# fboard.net
KiCad netlist of a schematic drawn in EAGLE
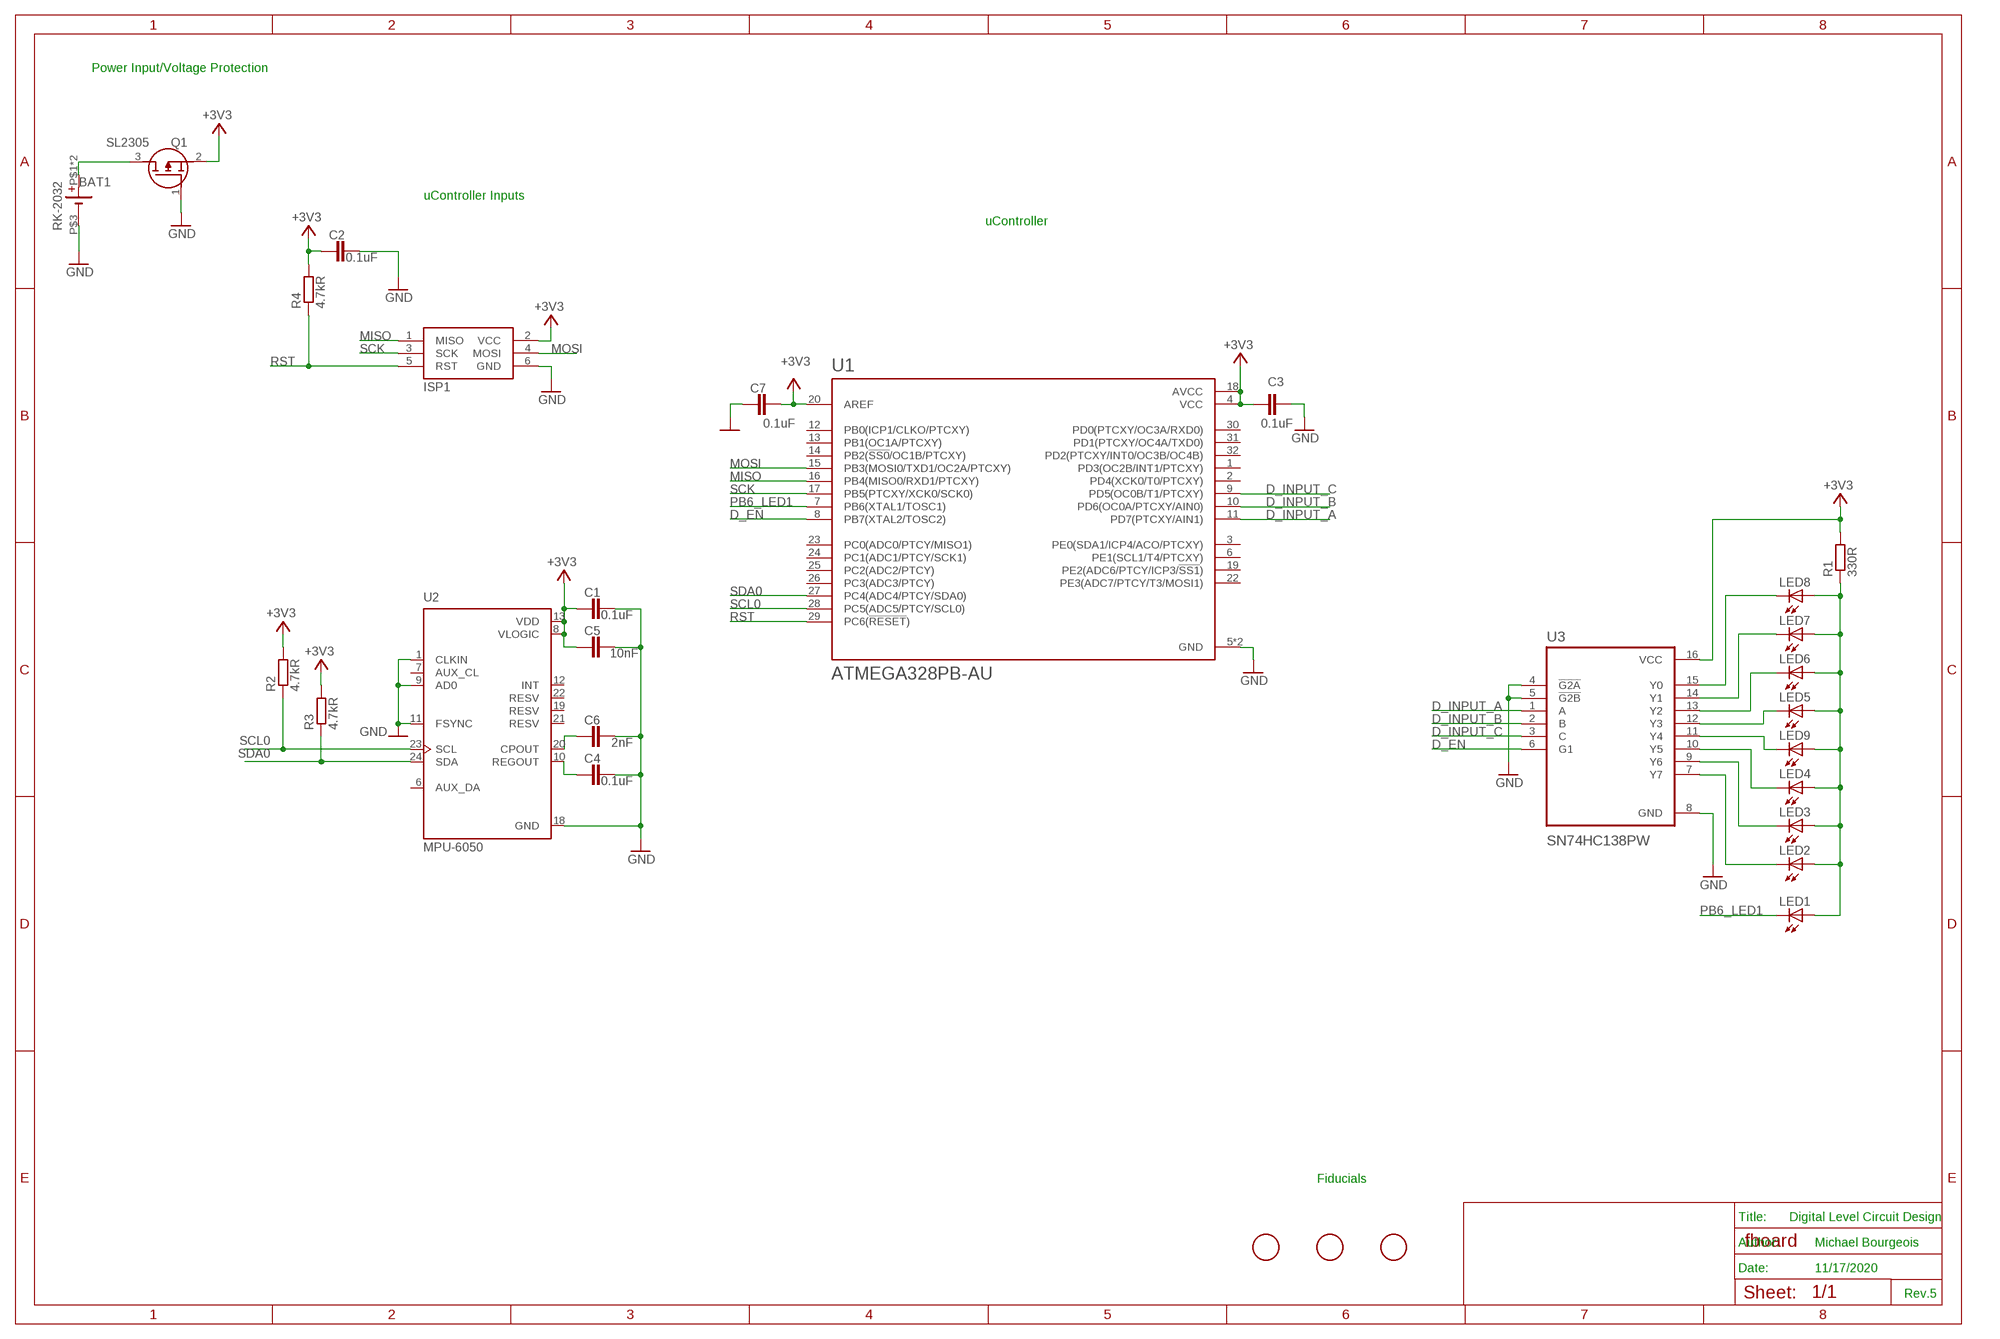
[diagram p0: schematic, sheet 1]

(export (version "E")
  (design (tool "Eeschema 10.0.6"))
  (components
    (comp (ref "BAT1")
      (value "RK-2032")
      (footprint "eagle-import:RK-2032")
      (libsource (lib "eagle-import") (part "RK-2032"))
    )
    (comp (ref "C1")
      (value "0.1uF")
      (footprint "eagle-import:C0805")
      (libsource (lib "eagle-import") (part "C-EUC0805"))
    )
    (comp (ref "C2")
      (value "0.1uF")
      (footprint "eagle-import:C0805")
      (libsource (lib "eagle-import") (part "C-EUC0805"))
    )
    (comp (ref "C3")
      (value "0.1uF")
      (footprint "eagle-import:C0805")
      (libsource (lib "eagle-import") (part "C-EUC0805"))
    )
    (comp (ref "C4")
      (value "0.1uF")
      (footprint "eagle-import:C0805")
      (libsource (lib "eagle-import") (part "C-EUC0805"))
    )
    (comp (ref "C5")
      (value "10nF")
      (footprint "eagle-import:C0805")
      (libsource (lib "eagle-import") (part "C-EUC0805"))
    )
    (comp (ref "C6")
      (value "2nF")
      (footprint "eagle-import:C0805")
      (libsource (lib "eagle-import") (part "C-EUC0805"))
    )
    (comp (ref "C7")
      (value "0.1uF")
      (footprint "eagle-import:C0805")
      (libsource (lib "eagle-import") (part "C-EUC0805"))
    )
    (comp (ref "ISP1")
      (value "AVRISP-6")
      (footprint "eagle-import:AVRISP")
      (libsource (lib "eagle-import") (part "AVRISP-6"))
    )
    (comp (ref "LED1")
      (value "LEDCHIP-LED0805")
      (footprint "eagle-import:CHIP-LED0805")
      (libsource (lib "eagle-import") (part "LEDCHIP-LED0805"))
    )
    (comp (ref "LED2")
      (value "LEDCHIP-LED0805")
      (footprint "eagle-import:CHIP-LED0805")
      (libsource (lib "eagle-import") (part "LEDCHIP-LED0805"))
    )
    (comp (ref "LED3")
      (value "LEDCHIP-LED0805")
      (footprint "eagle-import:CHIP-LED0805")
      (libsource (lib "eagle-import") (part "LEDCHIP-LED0805"))
    )
    (comp (ref "LED4")
      (value "LEDCHIP-LED0805")
      (footprint "eagle-import:CHIP-LED0805")
      (libsource (lib "eagle-import") (part "LEDCHIP-LED0805"))
    )
    (comp (ref "LED5")
      (value "LEDCHIP-LED0805")
      (footprint "eagle-import:CHIP-LED0805")
      (libsource (lib "eagle-import") (part "LEDCHIP-LED0805"))
    )
    (comp (ref "LED6")
      (value "LEDCHIP-LED0805")
      (footprint "eagle-import:CHIP-LED0805")
      (libsource (lib "eagle-import") (part "LEDCHIP-LED0805"))
    )
    (comp (ref "LED7")
      (value "LEDCHIP-LED0805")
      (footprint "eagle-import:CHIP-LED0805")
      (libsource (lib "eagle-import") (part "LEDCHIP-LED0805"))
    )
    (comp (ref "LED8")
      (value "LEDCHIP-LED0805")
      (footprint "eagle-import:CHIP-LED0805")
      (libsource (lib "eagle-import") (part "LEDCHIP-LED0805"))
    )
    (comp (ref "LED9")
      (value "LEDCHIPLED_0805")
      (footprint "eagle-import:CHIPLED_0805")
      (libsource (lib "eagle-import") (part "LEDCHIPLED_0805"))
    )
    (comp (ref "Q1")
      (value "SL2305")
      (footprint "eagle-import:SOT95P240X115-3N")
      (libsource (lib "eagle-import") (part "SL2305"))
    )
    (comp (ref "R1")
      (value "330R")
      (footprint "eagle-import:R0805")
      (libsource (lib "eagle-import") (part "R-EU_R0805"))
    )
    (comp (ref "R2")
      (value "4.7kR")
      (footprint "eagle-import:R0805")
      (libsource (lib "eagle-import") (part "R-EU_R0805"))
    )
    (comp (ref "R3")
      (value "4.7kR")
      (footprint "eagle-import:R0805")
      (libsource (lib "eagle-import") (part "R-EU_R0805"))
    )
    (comp (ref "R4")
      (value "4.7kR")
      (footprint "eagle-import:R0805")
      (libsource (lib "eagle-import") (part "R-EU_R0805"))
    )
    (comp (ref "U$4")
      (value "FIDUCIAL")
      (footprint "eagle-import:FIDUCIAL_1MM")
      (libsource (lib "eagle-import") (part "FIDUCIAL"))
    )
    (comp (ref "U$5")
      (value "FIDUCIAL")
      (footprint "eagle-import:FIDUCIAL_1MM")
      (libsource (lib "eagle-import") (part "FIDUCIAL"))
    )
    (comp (ref "U$6")
      (value "FIDUCIAL")
      (footprint "eagle-import:FIDUCIAL_1MM")
      (libsource (lib "eagle-import") (part "FIDUCIAL"))
    )
    (comp (ref "U1")
      (value "ATMEGA328PB-AU")
      (footprint "eagle-import:QFP80P900X900X120-32N")
      (fields (field (name "MF") "Microchip Technology / Atmel"))
      (libsource (lib "eagle-import") (part "ATMEGA328PB-AU"))
    )
    (comp (ref "U2")
      (value "MPU-6050")
      (footprint "eagle-import:QFN50P400X400X95-24N")
      (fields (field (name "DIGI-KEY_PART_NUMBER") "1428-1007-1-ND") (field (name "MF") "TDK InvenSense"))
      (libsource (lib "eagle-import") (part "MPU-6050"))
    )
    (comp (ref "U3")
      (value "SN74HC138PW")
      (footprint "eagle-import:SOP65P640X120-16N")
      (fields (field (name "MF") "Texas Instruments"))
      (libsource (lib "eagle-import") (part "SN74HC138PW"))
    )
  )
  (nets
    (net (code "1") (name "+3V3") (class "Default")
      (node (ref "C1") (pin "1") (pinfunction "1_1") (pintype "passive"))
      (node (ref "C2") (pin "1") (pinfunction "1_1") (pintype "passive"))
      (node (ref "C3") (pin "1") (pinfunction "1_1") (pintype "passive"))
      (node (ref "C5") (pin "1") (pinfunction "1_1") (pintype "passive"))
      (node (ref "C7") (pin "1") (pinfunction "1_1") (pintype "passive"))
      (node (ref "ISP1") (pin "2") (pinfunction "VCC_2") (pintype "power_in"))
      (node (ref "Q1") (pin "2") (pinfunction "S_2") (pintype "bidirectional"))
      (node (ref "R1") (pin "2") (pinfunction "2_2") (pintype "passive"))
      (node (ref "R2") (pin "2") (pinfunction "2_2") (pintype "passive"))
      (node (ref "R3") (pin "2") (pinfunction "2_2") (pintype "passive"))
      (node (ref "R4") (pin "2") (pinfunction "2_2") (pintype "passive"))
      (node (ref "U1") (pin "18") (pinfunction "AVCC_18") (pintype "power_in"))
      (node (ref "U1") (pin "20") (pinfunction "AREF_20") (pintype "input"))
      (node (ref "U1") (pin "4") (pinfunction "VCC_4") (pintype "power_in"))
      (node (ref "U2") (pin "13") (pinfunction "VDD_13") (pintype "power_in"))
      (node (ref "U2") (pin "8") (pinfunction "VLOGIC_8") (pintype "power_in"))
      (node (ref "U3") (pin "16") (pinfunction "VCC_16") (pintype "power_in"))
    )
    (net (code "2") (name "/D_EN") (class "Default")
      (node (ref "U1") (pin "8") (pinfunction "PB7(XTAL2/TOSC2)_8") (pintype "bidirectional"))
      (node (ref "U3") (pin "6") (pinfunction "G1_6") (pintype "input"))
    )
    (net (code "3") (name "/D_INPUT_A") (class "Default")
      (node (ref "U1") (pin "11") (pinfunction "PD7(PTCXY/AIN1)_11") (pintype "bidirectional"))
      (node (ref "U3") (pin "1") (pinfunction "A_1") (pintype "input"))
    )
    (net (code "4") (name "/D_INPUT_B") (class "Default")
      (node (ref "U1") (pin "10") (pinfunction "PD6(OC0A/PTCXY/AIN0)_10") (pintype "bidirectional"))
      (node (ref "U3") (pin "2") (pinfunction "B_2") (pintype "input"))
    )
    (net (code "5") (name "/D_INPUT_C") (class "Default")
      (node (ref "U1") (pin "9") (pinfunction "PD5(OC0B/T1/PTCXY)_9") (pintype "bidirectional"))
      (node (ref "U3") (pin "3") (pinfunction "C_3") (pintype "input"))
    )
    (net (code "6") (name "/MISO") (class "Default")
      (node (ref "ISP1") (pin "1") (pinfunction "MISO_1") (pintype "input"))
      (node (ref "U1") (pin "16") (pinfunction "PB4(MISO0/RXD1/PTCXY)_16") (pintype "bidirectional"))
    )
    (net (code "7") (name "/MOSI") (class "Default")
      (node (ref "ISP1") (pin "4") (pinfunction "MOSI_4") (pintype "output"))
      (node (ref "U1") (pin "15") (pinfunction "PB3(MOSI0/TXD1/OC2A/PTCXY)_15") (pintype "bidirectional"))
    )
    (net (code "8") (name "/PB6_LED1") (class "Default")
      (node (ref "LED1") (pin "C") (pinfunction "C_C") (pintype "passive"))
      (node (ref "U1") (pin "7") (pinfunction "PB6(XTAL1/TOSC1)_7") (pintype "bidirectional"))
    )
    (net (code "9") (name "/RST") (class "Default")
      (node (ref "ISP1") (pin "5") (pinfunction "RST_5") (pintype "output"))
      (node (ref "R4") (pin "1") (pinfunction "1_1") (pintype "passive"))
      (node (ref "U1") (pin "29") (pinfunction "PC6(~{RESET})_29") (pintype "bidirectional"))
    )
    (net (code "10") (name "/SCK") (class "Default")
      (node (ref "ISP1") (pin "3") (pinfunction "SCK_3") (pintype "output"))
      (node (ref "U1") (pin "17") (pinfunction "PB5(PTCXY/XCK0/SCK0)_17") (pintype "bidirectional"))
    )
    (net (code "11") (name "/SCL0") (class "Default")
      (node (ref "R2") (pin "1") (pinfunction "1_1") (pintype "passive"))
      (node (ref "U1") (pin "28") (pinfunction "PC5(ADC5/PTCY/SCL0)_28") (pintype "bidirectional"))
      (node (ref "U2") (pin "23") (pinfunction "SCL_23") (pintype "input"))
    )
    (net (code "12") (name "/SDA0") (class "Default")
      (node (ref "R3") (pin "1") (pinfunction "1_1") (pintype "passive"))
      (node (ref "U1") (pin "27") (pinfunction "PC4(ADC4/PTCY/SDA0)_27") (pintype "bidirectional"))
      (node (ref "U2") (pin "24") (pinfunction "SDA_24") (pintype "bidirectional"))
    )
    (net (code "13") (name "GND") (class "Default")
      (node (ref "BAT1") (pin "P$3") (pinfunction "-_P$3") (pintype "passive"))
      (node (ref "C1") (pin "2") (pinfunction "2_2") (pintype "passive"))
      (node (ref "C2") (pin "2") (pinfunction "2_2") (pintype "passive"))
      (node (ref "C3") (pin "2") (pinfunction "2_2") (pintype "passive"))
      (node (ref "C4") (pin "2") (pinfunction "2_2") (pintype "passive"))
      (node (ref "C5") (pin "2") (pinfunction "2_2") (pintype "passive"))
      (node (ref "C6") (pin "2") (pinfunction "2_2") (pintype "passive"))
      (node (ref "C7") (pin "2") (pinfunction "2_2") (pintype "passive"))
      (node (ref "ISP1") (pin "6") (pinfunction "GND_6") (pintype "power_in"))
      (node (ref "Q1") (pin "1") (pinfunction "G_1") (pintype "bidirectional"))
      (node (ref "U1") (pin "21") (pinfunction "GND_21") (pintype "power_in"))
      (node (ref "U1") (pin "5") (pinfunction "GND_5") (pintype "power_in"))
      (node (ref "U2") (pin "1") (pinfunction "CLKIN_1") (pintype "input"))
      (node (ref "U2") (pin "11") (pinfunction "FSYNC_11") (pintype "input"))
      (node (ref "U2") (pin "18") (pinfunction "GND_18") (pintype "power_in"))
      (node (ref "U2") (pin "9") (pinfunction "AD0_9") (pintype "input"))
      (node (ref "U3") (pin "4") (pinfunction "~{G2A}_4") (pintype "input"))
      (node (ref "U3") (pin "5") (pinfunction "~{G2B}_5") (pintype "input"))
      (node (ref "U3") (pin "8") (pinfunction "GND_8") (pintype "power_in"))
    )
    (net (code "14") (name "Net-(LED1-PadA)") (class "Default")
      (node (ref "LED1") (pin "A") (pinfunction "A_A") (pintype "passive"))
      (node (ref "LED2") (pin "A") (pinfunction "A_A") (pintype "passive"))
      (node (ref "LED3") (pin "A") (pinfunction "A_A") (pintype "passive"))
      (node (ref "LED4") (pin "A") (pinfunction "A_A") (pintype "passive"))
      (node (ref "LED5") (pin "A") (pinfunction "A_A") (pintype "passive"))
      (node (ref "LED6") (pin "A") (pinfunction "A_A") (pintype "passive"))
      (node (ref "LED7") (pin "A") (pinfunction "A_A") (pintype "passive"))
      (node (ref "LED8") (pin "A") (pinfunction "A_A") (pintype "passive"))
      (node (ref "LED9") (pin "A") (pinfunction "A_A") (pintype "passive"))
      (node (ref "R1") (pin "1") (pinfunction "1_1") (pintype "passive"))
    )
    (net (code "15") (name "Net-(Q1-D)") (class "Default")
      (node (ref "BAT1") (pin "P$1") (pinfunction "+_P$1") (pintype "passive"))
      (node (ref "BAT1") (pin "P$2") (pinfunction "+_P$2") (pintype "passive"))
      (node (ref "Q1") (pin "3") (pinfunction "D_3") (pintype "bidirectional"))
    )
    (net (code "16") (name "Net-(U2-CPOUT)") (class "Default")
      (node (ref "C6") (pin "1") (pinfunction "1_1") (pintype "passive"))
      (node (ref "U2") (pin "20") (pinfunction "CPOUT_20") (pintype "passive"))
    )
    (net (code "17") (name "Net-(U2-REGOUT)") (class "Default")
      (node (ref "C4") (pin "1") (pinfunction "1_1") (pintype "passive"))
      (node (ref "U2") (pin "10") (pinfunction "REGOUT_10") (pintype "passive"))
    )
    (net (code "18") (name "Net-(U3-Y0)") (class "Default")
      (node (ref "LED8") (pin "C") (pinfunction "C_C") (pintype "passive"))
      (node (ref "U3") (pin "15") (pinfunction "Y0_15") (pintype "output"))
    )
    (net (code "19") (name "Net-(U3-Y1)") (class "Default")
      (node (ref "LED7") (pin "C") (pinfunction "C_C") (pintype "passive"))
      (node (ref "U3") (pin "14") (pinfunction "Y1_14") (pintype "output"))
    )
    (net (code "20") (name "Net-(U3-Y2)") (class "Default")
      (node (ref "LED6") (pin "C") (pinfunction "C_C") (pintype "passive"))
      (node (ref "U3") (pin "13") (pinfunction "Y2_13") (pintype "output"))
    )
    (net (code "21") (name "Net-(U3-Y3)") (class "Default")
      (node (ref "LED5") (pin "C") (pinfunction "C_C") (pintype "passive"))
      (node (ref "U3") (pin "12") (pinfunction "Y3_12") (pintype "output"))
    )
    (net (code "22") (name "Net-(U3-Y4)") (class "Default")
      (node (ref "LED9") (pin "C") (pinfunction "C_C") (pintype "passive"))
      (node (ref "U3") (pin "11") (pinfunction "Y4_11") (pintype "output"))
    )
    (net (code "23") (name "Net-(U3-Y5)") (class "Default")
      (node (ref "LED4") (pin "C") (pinfunction "C_C") (pintype "passive"))
      (node (ref "U3") (pin "10") (pinfunction "Y5_10") (pintype "output"))
    )
    (net (code "24") (name "Net-(U3-Y6)") (class "Default")
      (node (ref "LED3") (pin "C") (pinfunction "C_C") (pintype "passive"))
      (node (ref "U3") (pin "9") (pinfunction "Y6_9") (pintype "output"))
    )
    (net (code "25") (name "Net-(U3-Y7)") (class "Default")
      (node (ref "LED2") (pin "C") (pinfunction "C_C") (pintype "passive"))
      (node (ref "U3") (pin "7") (pinfunction "Y7_7") (pintype "output"))
    )
    (net (code "26") (name "unconnected-(U1-PB0(ICP1{slash}CLKO{slash}PTCXY)-Pad12)") (class "Default")
      (node (ref "U1") (pin "12") (pinfunction "PB0(ICP1/CLKO/PTCXY)_12") (pintype "bidirectional"))
    )
    (net (code "27") (name "unconnected-(U1-PB1(OC1A{slash}PTCXY)-Pad13)") (class "Default")
      (node (ref "U1") (pin "13") (pinfunction "PB1(OC1A/PTCXY)_13") (pintype "bidirectional"))
    )
    (net (code "28") (name "unconnected-(U1-PB2(~{SS0}{slash}OC1B{slash}PTCXY)-Pad14)") (class "Default")
      (node (ref "U1") (pin "14") (pinfunction "PB2(~{SS0}/OC1B/PTCXY)_14") (pintype "bidirectional"))
    )
    (net (code "29") (name "unconnected-(U1-PC0(ADC0{slash}PTCY{slash}MISO1)-Pad23)") (class "Default")
      (node (ref "U1") (pin "23") (pinfunction "PC0(ADC0/PTCY/MISO1)_23") (pintype "bidirectional"))
    )
    (net (code "30") (name "unconnected-(U1-PC1(ADC1{slash}PTCY{slash}SCK1)-Pad24)") (class "Default")
      (node (ref "U1") (pin "24") (pinfunction "PC1(ADC1/PTCY/SCK1)_24") (pintype "bidirectional"))
    )
    (net (code "31") (name "unconnected-(U1-PC2(ADC2{slash}PTCY)-Pad25)") (class "Default")
      (node (ref "U1") (pin "25") (pinfunction "PC2(ADC2/PTCY)_25") (pintype "bidirectional"))
    )
    (net (code "32") (name "unconnected-(U1-PC3(ADC3{slash}PTCY)-Pad26)") (class "Default")
      (node (ref "U1") (pin "26") (pinfunction "PC3(ADC3/PTCY)_26") (pintype "bidirectional"))
    )
    (net (code "33") (name "unconnected-(U1-PD0(PTCXY{slash}OC3A{slash}RXD0)-Pad30)") (class "Default")
      (node (ref "U1") (pin "30") (pinfunction "PD0(PTCXY/OC3A/RXD0)_30") (pintype "bidirectional"))
    )
    (net (code "34") (name "unconnected-(U1-PD1(PTCXY{slash}OC4A{slash}TXD0)-Pad31)") (class "Default")
      (node (ref "U1") (pin "31") (pinfunction "PD1(PTCXY/OC4A/TXD0)_31") (pintype "bidirectional"))
    )
    (net (code "35") (name "unconnected-(U1-PD2(PTCXY{slash}INT0{slash}OC3B{slash}OC4B)-Pad32)") (class "Default")
      (node (ref "U1") (pin "32") (pinfunction "PD2(PTCXY/INT0/OC3B/OC4B)_32") (pintype "bidirectional"))
    )
    (net (code "36") (name "unconnected-(U1-PD3(OC2B{slash}INT1{slash}PTCXY)-Pad1)") (class "Default")
      (node (ref "U1") (pin "1") (pinfunction "PD3(OC2B/INT1/PTCXY)_1") (pintype "bidirectional"))
    )
    (net (code "37") (name "unconnected-(U1-PD4(XCK0{slash}T0{slash}PTCXY)-Pad2)") (class "Default")
      (node (ref "U1") (pin "2") (pinfunction "PD4(XCK0/T0/PTCXY)_2") (pintype "bidirectional"))
    )
    (net (code "38") (name "unconnected-(U1-PE0(SDA1{slash}ICP4{slash}ACO{slash}PTCXY)-Pad3)") (class "Default")
      (node (ref "U1") (pin "3") (pinfunction "PE0(SDA1/ICP4/ACO/PTCXY)_3") (pintype "bidirectional"))
    )
    (net (code "39") (name "unconnected-(U1-PE1(SCL1{slash}T4{slash}PTCXY)-Pad6)") (class "Default")
      (node (ref "U1") (pin "6") (pinfunction "PE1(SCL1/T4/PTCXY)_6") (pintype "bidirectional"))
    )
    (net (code "40") (name "unconnected-(U1-PE2(ADC6{slash}PTCY{slash}ICP3{slash}~{SS1})-Pad19)") (class "Default")
      (node (ref "U1") (pin "19") (pinfunction "PE2(ADC6/PTCY/ICP3/~{SS1})_19") (pintype "bidirectional"))
    )
    (net (code "41") (name "unconnected-(U1-PE3(ADC7{slash}PTCY{slash}T3{slash}MOSI1)-Pad22)") (class "Default")
      (node (ref "U1") (pin "22") (pinfunction "PE3(ADC7/PTCY/T3/MOSI1)_22") (pintype "bidirectional"))
    )
    (net (code "42") (name "unconnected-(U2-AUX_CL-Pad7)") (class "Default")
      (node (ref "U2") (pin "7") (pinfunction "AUX_CL_7") (pintype "input"))
    )
    (net (code "43") (name "unconnected-(U2-AUX_DA-Pad6)") (class "Default")
      (node (ref "U2") (pin "6") (pinfunction "AUX_DA_6") (pintype "bidirectional"))
    )
    (net (code "44") (name "unconnected-(U2-INT-Pad12)") (class "Default")
      (node (ref "U2") (pin "12") (pinfunction "INT_12") (pintype "output"))
    )
    (net (code "45") (name "unconnected-(U2-RESV-Pad19)") (class "Default")
      (node (ref "U2") (pin "19") (pinfunction "RESV_19") (pintype "passive"))
    )
    (net (code "46") (name "unconnected-(U2-RESV-Pad21)") (class "Default")
      (node (ref "U2") (pin "21") (pinfunction "RESV_21") (pintype "passive"))
    )
    (net (code "47") (name "unconnected-(U2-RESV-Pad22)") (class "Default")
      (node (ref "U2") (pin "22") (pinfunction "RESV_22") (pintype "passive"))
    )
  )
)
